# TourisTech.net
KiCad netlist of a schematic drawn in EAGLE
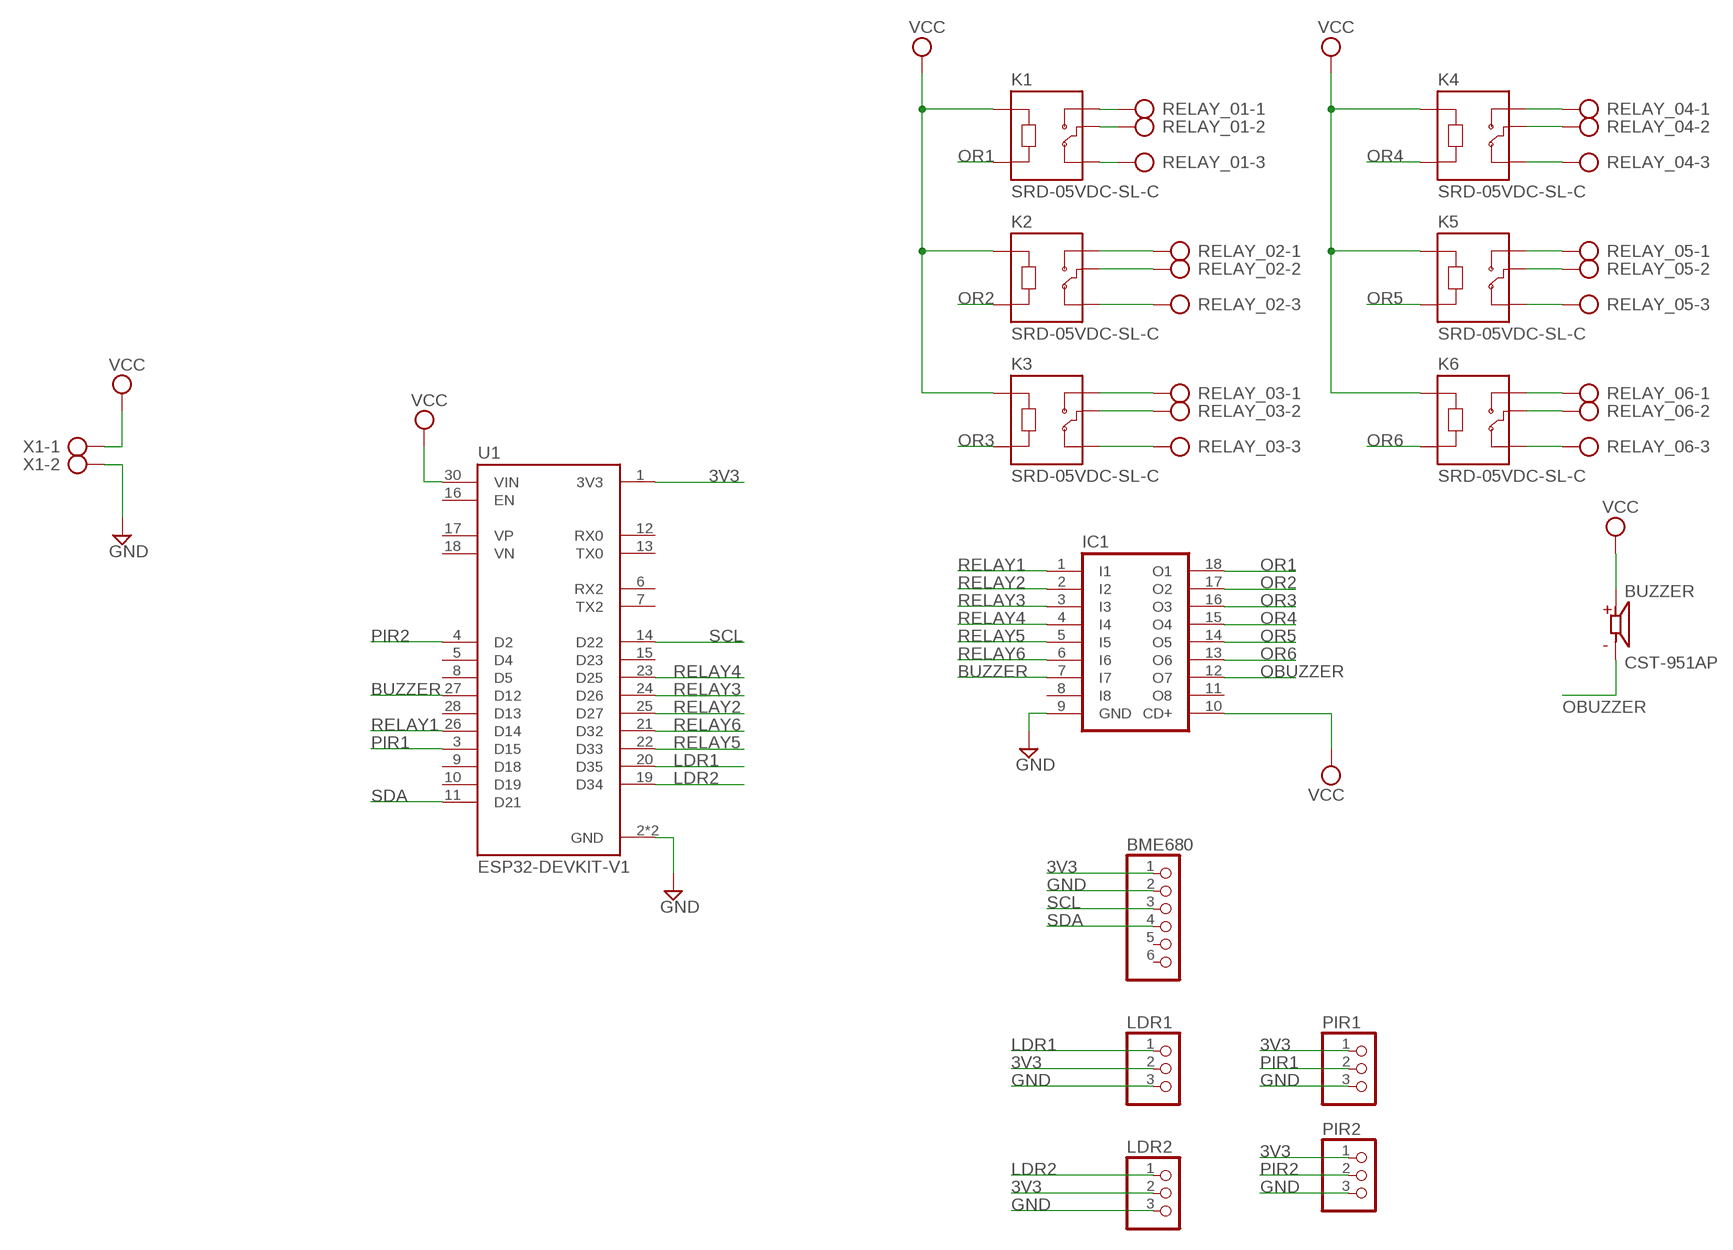
[diagram p0: schematic, sheet 1]

(export (version "E")
  (design (tool "Eeschema 10.0.6"))
  (components
    (comp (ref "BME680")
      (value "PINHD-1X6")
      (footprint "eagle-import:1X06")
      (libsource (lib "eagle-import") (part "PINHD-1X6"))
    )
    (comp (ref "BUZZER")
      (value "CST-951AP")
      (footprint "eagle-import:CUI_CST-951AP")
      (fields (field (name "MF") "CUI Devices"))
      (libsource (lib "eagle-import") (part "CST-951AP"))
    )
    (comp (ref "IC1")
      (value "ULN2803A")
      (footprint "eagle-import:DIL18")
      (libsource (lib "eagle-import") (part "ULN2803A"))
    )
    (comp (ref "K1")
      (value "SRD-05VDC-SL-C")
      (footprint "eagle-import:RELAY_SRD-05VDC-SL-C")
      (fields (field (name "MF") "Songle Relay"))
      (libsource (lib "eagle-import") (part "SRD-05VDC-SL-C"))
    )
    (comp (ref "K2")
      (value "SRD-05VDC-SL-C")
      (footprint "eagle-import:RELAY_SRD-05VDC-SL-C")
      (fields (field (name "MF") "Songle Relay"))
      (libsource (lib "eagle-import") (part "SRD-05VDC-SL-C"))
    )
    (comp (ref "K3")
      (value "SRD-05VDC-SL-C")
      (footprint "eagle-import:RELAY_SRD-05VDC-SL-C")
      (fields (field (name "MF") "Songle Relay"))
      (libsource (lib "eagle-import") (part "SRD-05VDC-SL-C"))
    )
    (comp (ref "K4")
      (value "SRD-05VDC-SL-C")
      (footprint "eagle-import:RELAY_SRD-05VDC-SL-C")
      (fields (field (name "MF") "Songle Relay"))
      (libsource (lib "eagle-import") (part "SRD-05VDC-SL-C"))
    )
    (comp (ref "K5")
      (value "SRD-05VDC-SL-C")
      (footprint "eagle-import:RELAY_SRD-05VDC-SL-C")
      (fields (field (name "MF") "Songle Relay"))
      (libsource (lib "eagle-import") (part "SRD-05VDC-SL-C"))
    )
    (comp (ref "K6")
      (value "SRD-05VDC-SL-C")
      (footprint "eagle-import:RELAY_SRD-05VDC-SL-C")
      (fields (field (name "MF") "Songle Relay"))
      (libsource (lib "eagle-import") (part "SRD-05VDC-SL-C"))
    )
    (comp (ref "LDR1")
      (value "PINHD-1X3")
      (footprint "eagle-import:1X03")
      (libsource (lib "eagle-import") (part "PINHD-1X3"))
    )
    (comp (ref "LDR2")
      (value "PINHD-1X3")
      (footprint "eagle-import:1X03")
      (libsource (lib "eagle-import") (part "PINHD-1X3"))
    )
    (comp (ref "PIR1")
      (value "PINHD-1X3")
      (footprint "eagle-import:1X03")
      (libsource (lib "eagle-import") (part "PINHD-1X3"))
    )
    (comp (ref "PIR2")
      (value "PINHD-1X3")
      (footprint "eagle-import:1X03")
      (libsource (lib "eagle-import") (part "PINHD-1X3"))
    )
    (comp (ref "RELAY_01")
      (value "AK300/3")
      (footprint "eagle-import:AK300_3")
      (libsource (lib "eagle-import") (part "AK300/3"))
    )
    (comp (ref "RELAY_02")
      (value "AK300/3")
      (footprint "eagle-import:AK300_3")
      (libsource (lib "eagle-import") (part "AK300/3"))
    )
    (comp (ref "RELAY_03")
      (value "AK300/3")
      (footprint "eagle-import:AK300_3")
      (libsource (lib "eagle-import") (part "AK300/3"))
    )
    (comp (ref "RELAY_04")
      (value "AK300/3")
      (footprint "eagle-import:AK300_3")
      (libsource (lib "eagle-import") (part "AK300/3"))
    )
    (comp (ref "RELAY_05")
      (value "AK300/3")
      (footprint "eagle-import:AK300_3")
      (libsource (lib "eagle-import") (part "AK300/3"))
    )
    (comp (ref "RELAY_06")
      (value "AK300/3")
      (footprint "eagle-import:AK300_3")
      (libsource (lib "eagle-import") (part "AK300/3"))
    )
    (comp (ref "U1")
      (value "ESP32-DEVKIT-V1")
      (footprint "eagle-import:MODULE_ESP32_DEVKIT_V1")
      (fields (field (name "MF") "Do it"))
      (libsource (lib "eagle-import") (part "ESP32-DEVKIT-V1"))
    )
    (comp (ref "X1")
      (value "AK300/2")
      (footprint "eagle-import:AK300_2")
      (libsource (lib "eagle-import") (part "AK300/2"))
    )
  )
  (nets
    (net (code "1") (name "/3V3") (class "Default")
      (node (ref "BME680") (pin "1") (pinfunction "1_1") (pintype "passive"))
      (node (ref "LDR1") (pin "2") (pinfunction "2_2") (pintype "passive"))
      (node (ref "LDR2") (pin "2") (pinfunction "2_2") (pintype "passive"))
      (node (ref "PIR1") (pin "1") (pinfunction "1_1") (pintype "passive"))
      (node (ref "PIR2") (pin "1") (pinfunction "1_1") (pintype "passive"))
      (node (ref "U1") (pin "1") (pinfunction "3V3_1") (pintype "output"))
    )
    (net (code "2") (name "/BUZZER") (class "Default")
      (node (ref "IC1") (pin "7") (pinfunction "I7_7") (pintype "input"))
      (node (ref "U1") (pin "27") (pinfunction "D12_27") (pintype "bidirectional"))
    )
    (net (code "3") (name "/LDR1") (class "Default")
      (node (ref "LDR1") (pin "1") (pinfunction "1_1") (pintype "passive"))
      (node (ref "U1") (pin "20") (pinfunction "D35_20") (pintype "bidirectional"))
    )
    (net (code "4") (name "/LDR2") (class "Default")
      (node (ref "LDR2") (pin "1") (pinfunction "1_1") (pintype "passive"))
      (node (ref "U1") (pin "19") (pinfunction "D34_19") (pintype "bidirectional"))
    )
    (net (code "5") (name "/OBUZZER") (class "Default")
      (node (ref "BUZZER") (pin "M") (pinfunction "M_M") (pintype "passive"))
      (node (ref "IC1") (pin "12") (pinfunction "O7_12") (pintype "open_collector"))
    )
    (net (code "6") (name "/OR1") (class "Default")
      (node (ref "IC1") (pin "18") (pinfunction "O1_18") (pintype "open_collector"))
      (node (ref "K1") (pin "A2") (pinfunction "A2_A2") (pintype "passive"))
    )
    (net (code "7") (name "/OR2") (class "Default")
      (node (ref "IC1") (pin "17") (pinfunction "O2_17") (pintype "open_collector"))
      (node (ref "K2") (pin "A2") (pinfunction "A2_A2") (pintype "passive"))
    )
    (net (code "8") (name "/OR3") (class "Default")
      (node (ref "IC1") (pin "16") (pinfunction "O3_16") (pintype "open_collector"))
      (node (ref "K3") (pin "A2") (pinfunction "A2_A2") (pintype "passive"))
    )
    (net (code "9") (name "/OR4") (class "Default")
      (node (ref "IC1") (pin "15") (pinfunction "O4_15") (pintype "open_collector"))
      (node (ref "K4") (pin "A2") (pinfunction "A2_A2") (pintype "passive"))
    )
    (net (code "10") (name "/OR5") (class "Default")
      (node (ref "IC1") (pin "14") (pinfunction "O5_14") (pintype "open_collector"))
      (node (ref "K5") (pin "A2") (pinfunction "A2_A2") (pintype "passive"))
    )
    (net (code "11") (name "/OR6") (class "Default")
      (node (ref "IC1") (pin "13") (pinfunction "O6_13") (pintype "open_collector"))
      (node (ref "K6") (pin "A2") (pinfunction "A2_A2") (pintype "passive"))
    )
    (net (code "12") (name "/PIR1") (class "Default")
      (node (ref "PIR1") (pin "2") (pinfunction "2_2") (pintype "passive"))
      (node (ref "U1") (pin "3") (pinfunction "D15_3") (pintype "bidirectional"))
    )
    (net (code "13") (name "/PIR2") (class "Default")
      (node (ref "PIR2") (pin "2") (pinfunction "2_2") (pintype "passive"))
      (node (ref "U1") (pin "4") (pinfunction "D2_4") (pintype "bidirectional"))
    )
    (net (code "14") (name "/RELAY1") (class "Default")
      (node (ref "IC1") (pin "1") (pinfunction "I1_1") (pintype "input"))
      (node (ref "U1") (pin "26") (pinfunction "D14_26") (pintype "bidirectional"))
    )
    (net (code "15") (name "/RELAY2") (class "Default")
      (node (ref "IC1") (pin "2") (pinfunction "I2_2") (pintype "input"))
      (node (ref "U1") (pin "25") (pinfunction "D27_25") (pintype "bidirectional"))
    )
    (net (code "16") (name "/RELAY3") (class "Default")
      (node (ref "IC1") (pin "3") (pinfunction "I3_3") (pintype "input"))
      (node (ref "U1") (pin "24") (pinfunction "D26_24") (pintype "bidirectional"))
    )
    (net (code "17") (name "/RELAY4") (class "Default")
      (node (ref "IC1") (pin "4") (pinfunction "I4_4") (pintype "input"))
      (node (ref "U1") (pin "23") (pinfunction "D25_23") (pintype "bidirectional"))
    )
    (net (code "18") (name "/RELAY5") (class "Default")
      (node (ref "IC1") (pin "5") (pinfunction "I5_5") (pintype "input"))
      (node (ref "U1") (pin "22") (pinfunction "D33_22") (pintype "bidirectional"))
    )
    (net (code "19") (name "/RELAY6") (class "Default")
      (node (ref "IC1") (pin "6") (pinfunction "I6_6") (pintype "input"))
      (node (ref "U1") (pin "21") (pinfunction "D32_21") (pintype "bidirectional"))
    )
    (net (code "20") (name "/SCL") (class "Default")
      (node (ref "BME680") (pin "3") (pinfunction "3_3") (pintype "passive"))
      (node (ref "U1") (pin "14") (pinfunction "D22_14") (pintype "bidirectional"))
    )
    (net (code "21") (name "/SDA") (class "Default")
      (node (ref "BME680") (pin "4") (pinfunction "4_4") (pintype "passive"))
      (node (ref "U1") (pin "11") (pinfunction "D21_11") (pintype "bidirectional"))
    )
    (net (code "22") (name "GND") (class "Default")
      (node (ref "BME680") (pin "2") (pinfunction "2_2") (pintype "passive"))
      (node (ref "IC1") (pin "9") (pinfunction "GND_9") (pintype "power_in"))
      (node (ref "LDR1") (pin "3") (pinfunction "3_3") (pintype "passive"))
      (node (ref "LDR2") (pin "3") (pinfunction "3_3") (pintype "passive"))
      (node (ref "PIR1") (pin "3") (pinfunction "3_3") (pintype "passive"))
      (node (ref "PIR2") (pin "3") (pinfunction "3_3") (pintype "passive"))
      (node (ref "U1") (pin "2") (pinfunction "GND_2") (pintype "power_in"))
      (node (ref "U1") (pin "29") (pinfunction "GND_29") (pintype "power_in"))
      (node (ref "X1") (pin "2") (pinfunction "KL_2") (pintype "passive"))
    )
    (net (code "23") (name "Net-(RELAY_01A-KL)") (class "Default")
      (node (ref "K1") (pin "NO") (pinfunction "NO_NO") (pintype "passive"))
      (node (ref "RELAY_01") (pin "1") (pinfunction "KL_1") (pintype "passive"))
    )
    (net (code "24") (name "Net-(RELAY_01B-KL)") (class "Default")
      (node (ref "K1") (pin "COM") (pinfunction "COM_COM") (pintype "passive"))
      (node (ref "RELAY_01") (pin "2") (pinfunction "KL_2") (pintype "passive"))
    )
    (net (code "25") (name "Net-(RELAY_01C-KL)") (class "Default")
      (node (ref "K1") (pin "NC") (pinfunction "NC_NC") (pintype "passive"))
      (node (ref "RELAY_01") (pin "3") (pinfunction "KL_3") (pintype "passive"))
    )
    (net (code "26") (name "Net-(RELAY_02A-KL)") (class "Default")
      (node (ref "K2") (pin "NO") (pinfunction "NO_NO") (pintype "passive"))
      (node (ref "RELAY_02") (pin "1") (pinfunction "KL_1") (pintype "passive"))
    )
    (net (code "27") (name "Net-(RELAY_02B-KL)") (class "Default")
      (node (ref "K2") (pin "COM") (pinfunction "COM_COM") (pintype "passive"))
      (node (ref "RELAY_02") (pin "2") (pinfunction "KL_2") (pintype "passive"))
    )
    (net (code "28") (name "Net-(RELAY_02C-KL)") (class "Default")
      (node (ref "K2") (pin "NC") (pinfunction "NC_NC") (pintype "passive"))
      (node (ref "RELAY_02") (pin "3") (pinfunction "KL_3") (pintype "passive"))
    )
    (net (code "29") (name "Net-(RELAY_03A-KL)") (class "Default")
      (node (ref "K3") (pin "NO") (pinfunction "NO_NO") (pintype "passive"))
      (node (ref "RELAY_03") (pin "1") (pinfunction "KL_1") (pintype "passive"))
    )
    (net (code "30") (name "Net-(RELAY_03B-KL)") (class "Default")
      (node (ref "K3") (pin "COM") (pinfunction "COM_COM") (pintype "passive"))
      (node (ref "RELAY_03") (pin "2") (pinfunction "KL_2") (pintype "passive"))
    )
    (net (code "31") (name "Net-(RELAY_03C-KL)") (class "Default")
      (node (ref "K3") (pin "NC") (pinfunction "NC_NC") (pintype "passive"))
      (node (ref "RELAY_03") (pin "3") (pinfunction "KL_3") (pintype "passive"))
    )
    (net (code "32") (name "Net-(RELAY_04A-KL)") (class "Default")
      (node (ref "K4") (pin "NO") (pinfunction "NO_NO") (pintype "passive"))
      (node (ref "RELAY_04") (pin "1") (pinfunction "KL_1") (pintype "passive"))
    )
    (net (code "33") (name "Net-(RELAY_04B-KL)") (class "Default")
      (node (ref "K4") (pin "COM") (pinfunction "COM_COM") (pintype "passive"))
      (node (ref "RELAY_04") (pin "2") (pinfunction "KL_2") (pintype "passive"))
    )
    (net (code "34") (name "Net-(RELAY_04C-KL)") (class "Default")
      (node (ref "K4") (pin "NC") (pinfunction "NC_NC") (pintype "passive"))
      (node (ref "RELAY_04") (pin "3") (pinfunction "KL_3") (pintype "passive"))
    )
    (net (code "35") (name "Net-(RELAY_05A-KL)") (class "Default")
      (node (ref "K5") (pin "NO") (pinfunction "NO_NO") (pintype "passive"))
      (node (ref "RELAY_05") (pin "1") (pinfunction "KL_1") (pintype "passive"))
    )
    (net (code "36") (name "Net-(RELAY_05B-KL)") (class "Default")
      (node (ref "K5") (pin "COM") (pinfunction "COM_COM") (pintype "passive"))
      (node (ref "RELAY_05") (pin "2") (pinfunction "KL_2") (pintype "passive"))
    )
    (net (code "37") (name "Net-(RELAY_05C-KL)") (class "Default")
      (node (ref "K5") (pin "NC") (pinfunction "NC_NC") (pintype "passive"))
      (node (ref "RELAY_05") (pin "3") (pinfunction "KL_3") (pintype "passive"))
    )
    (net (code "38") (name "Net-(RELAY_06A-KL)") (class "Default")
      (node (ref "K6") (pin "NO") (pinfunction "NO_NO") (pintype "passive"))
      (node (ref "RELAY_06") (pin "1") (pinfunction "KL_1") (pintype "passive"))
    )
    (net (code "39") (name "Net-(RELAY_06B-KL)") (class "Default")
      (node (ref "K6") (pin "COM") (pinfunction "COM_COM") (pintype "passive"))
      (node (ref "RELAY_06") (pin "2") (pinfunction "KL_2") (pintype "passive"))
    )
    (net (code "40") (name "Net-(RELAY_06C-KL)") (class "Default")
      (node (ref "K6") (pin "NC") (pinfunction "NC_NC") (pintype "passive"))
      (node (ref "RELAY_06") (pin "3") (pinfunction "KL_3") (pintype "passive"))
    )
    (net (code "41") (name "VCC") (class "Default")
      (node (ref "BUZZER") (pin "P") (pinfunction "P_P") (pintype "passive"))
      (node (ref "IC1") (pin "10") (pinfunction "CD+_10") (pintype "passive"))
      (node (ref "K1") (pin "A1") (pinfunction "A1_A1") (pintype "passive"))
      (node (ref "K2") (pin "A1") (pinfunction "A1_A1") (pintype "passive"))
      (node (ref "K3") (pin "A1") (pinfunction "A1_A1") (pintype "passive"))
      (node (ref "K4") (pin "A1") (pinfunction "A1_A1") (pintype "passive"))
      (node (ref "K5") (pin "A1") (pinfunction "A1_A1") (pintype "passive"))
      (node (ref "K6") (pin "A1") (pinfunction "A1_A1") (pintype "passive"))
      (node (ref "U1") (pin "30") (pinfunction "VIN_30") (pintype "input"))
      (node (ref "X1") (pin "1") (pinfunction "KL_1") (pintype "passive"))
    )
    (net (code "42") (name "unconnected-(BME680-Pad5)") (class "Default")
      (node (ref "BME680") (pin "5") (pinfunction "5_5") (pintype "passive"))
    )
    (net (code "43") (name "unconnected-(BME680-Pad6)") (class "Default")
      (node (ref "BME680") (pin "6") (pinfunction "6_6") (pintype "passive"))
    )
    (net (code "44") (name "unconnected-(IC1-I8-Pad8)") (class "Default")
      (node (ref "IC1") (pin "8") (pinfunction "I8_8") (pintype "input"))
    )
    (net (code "45") (name "unconnected-(IC1-O8-Pad11)") (class "Default")
      (node (ref "IC1") (pin "11") (pinfunction "O8_11") (pintype "open_collector"))
    )
    (net (code "46") (name "unconnected-(U1-D4-Pad5)") (class "Default")
      (node (ref "U1") (pin "5") (pinfunction "D4_5") (pintype "bidirectional"))
    )
    (net (code "47") (name "unconnected-(U1-D5-Pad8)") (class "Default")
      (node (ref "U1") (pin "8") (pinfunction "D5_8") (pintype "bidirectional"))
    )
    (net (code "48") (name "unconnected-(U1-D13-Pad28)") (class "Default")
      (node (ref "U1") (pin "28") (pinfunction "D13_28") (pintype "bidirectional"))
    )
    (net (code "49") (name "unconnected-(U1-D18-Pad9)") (class "Default")
      (node (ref "U1") (pin "9") (pinfunction "D18_9") (pintype "bidirectional"))
    )
    (net (code "50") (name "unconnected-(U1-D19-Pad10)") (class "Default")
      (node (ref "U1") (pin "10") (pinfunction "D19_10") (pintype "bidirectional"))
    )
    (net (code "51") (name "unconnected-(U1-D23-Pad15)") (class "Default")
      (node (ref "U1") (pin "15") (pinfunction "D23_15") (pintype "bidirectional"))
    )
    (net (code "52") (name "unconnected-(U1-EN-Pad16)") (class "Default")
      (node (ref "U1") (pin "16") (pinfunction "EN_16") (pintype "input"))
    )
    (net (code "53") (name "unconnected-(U1-RX0-Pad12)") (class "Default")
      (node (ref "U1") (pin "12") (pinfunction "RX0_12") (pintype "input"))
    )
    (net (code "54") (name "unconnected-(U1-RX2-Pad6)") (class "Default")
      (node (ref "U1") (pin "6") (pinfunction "RX2_6") (pintype "input"))
    )
    (net (code "55") (name "unconnected-(U1-TX0-Pad13)") (class "Default")
      (node (ref "U1") (pin "13") (pinfunction "TX0_13") (pintype "output"))
    )
    (net (code "56") (name "unconnected-(U1-TX2-Pad7)") (class "Default")
      (node (ref "U1") (pin "7") (pinfunction "TX2_7") (pintype "output"))
    )
    (net (code "57") (name "unconnected-(U1-VN-Pad18)") (class "Default")
      (node (ref "U1") (pin "18") (pinfunction "VN_18") (pintype "bidirectional"))
    )
    (net (code "58") (name "unconnected-(U1-VP-Pad17)") (class "Default")
      (node (ref "U1") (pin "17") (pinfunction "VP_17") (pintype "bidirectional"))
    )
  )
)
